# eps_digital.net
KiCad netlist of a schematic drawn in Altium Designer
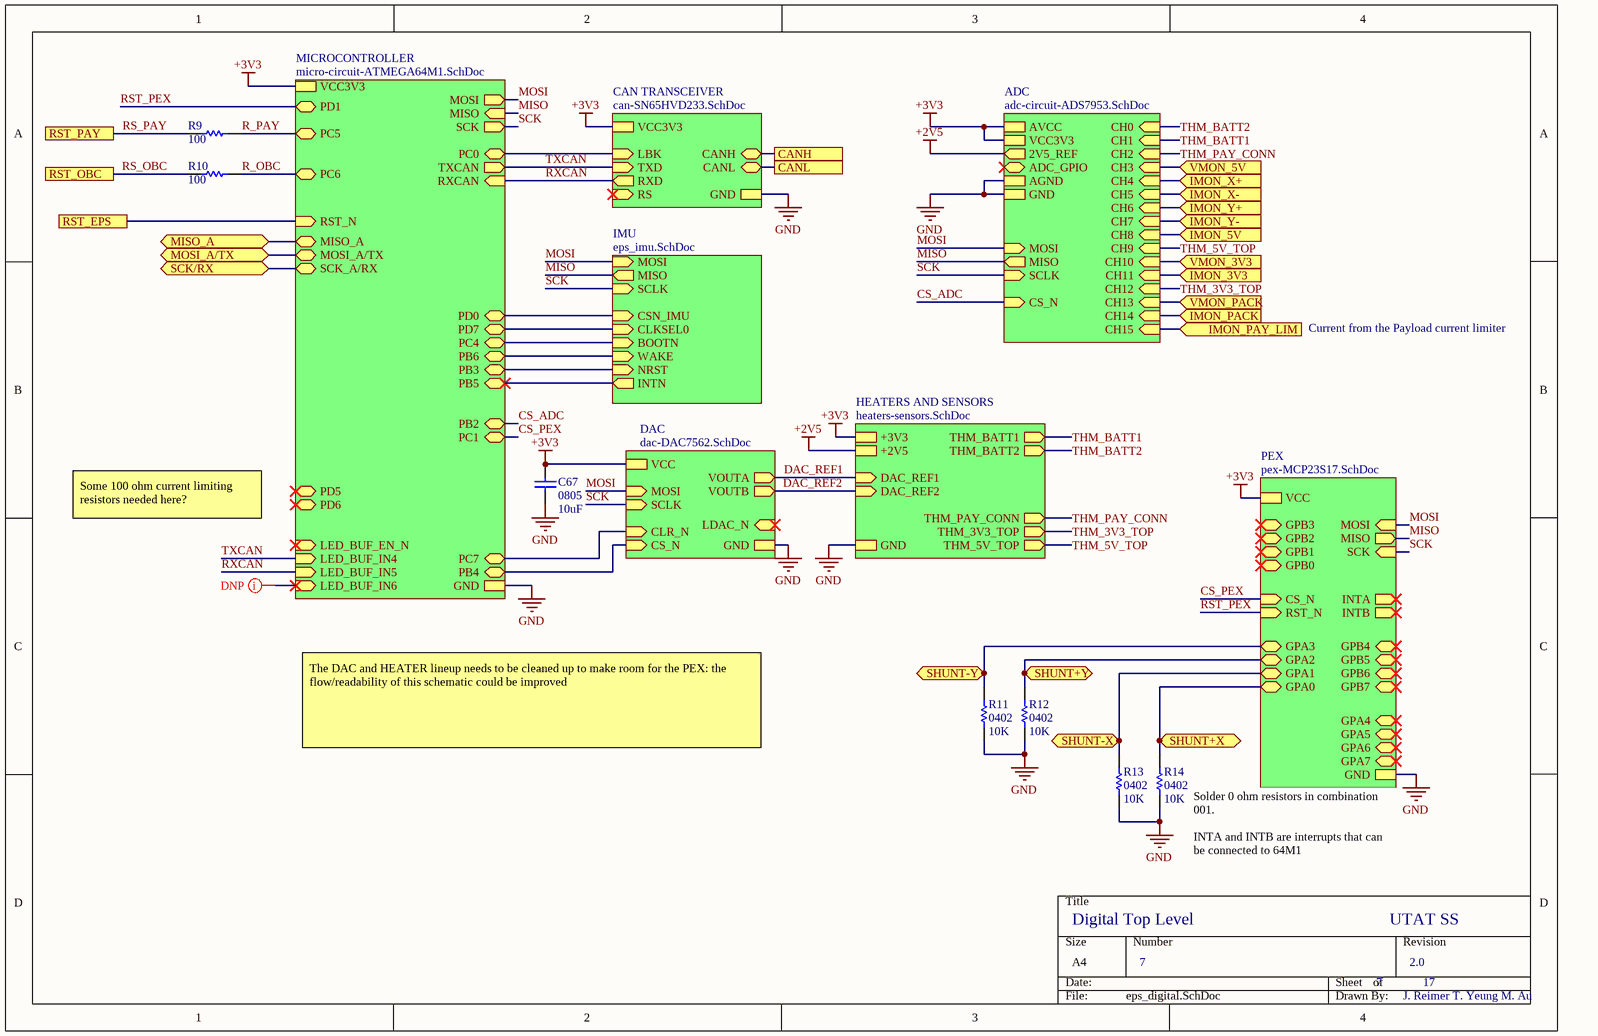
[diagram p0: eps_digital.SchDoc]

(export (version "E")
  (design (tool "Eeschema 10.0.6"))
  (components
    (comp (ref "C67")
      (value "0805")
      (footprint "CAP0805R")
      (description "0805 capacitor")
      (fields (field (name "ALTIUM_VALUE") "10uF"))
      (libsource (lib "heron-general") (part "CAP0805"))
    )
    (comp (ref "R9")
      (value "100")
      (footprint "RES0402R")
      (description "0402 resistor")
      (fields (field (name "Comment") "0402"))
      (libsource (lib "heron-general") (part "RES0402"))
    )
    (comp (ref "R10")
      (value "100")
      (footprint "RES0402R")
      (description "0402 resistor")
      (fields (field (name "Comment") "0402"))
      (libsource (lib "heron-general") (part "RES0402"))
    )
    (comp (ref "R11")
      (value "0402")
      (footprint "RES0402R")
      (description "0402 resistor")
      (fields (field (name "ALTIUM_VALUE") "10K"))
      (libsource (lib "heron-general") (part "RES0402"))
    )
    (comp (ref "R12")
      (value "0402")
      (footprint "RES0402R")
      (description "0402 resistor")
      (fields (field (name "ALTIUM_VALUE") "10K"))
      (libsource (lib "heron-general") (part "RES0402"))
    )
    (comp (ref "R13")
      (value "0402")
      (footprint "RES0402R")
      (description "0402 resistor")
      (fields (field (name "ALTIUM_VALUE") "10K"))
      (libsource (lib "heron-general") (part "RES0402"))
    )
    (comp (ref "R14")
      (value "0402")
      (footprint "RES0402R")
      (description "0402 resistor")
      (fields (field (name "ALTIUM_VALUE") "10K"))
      (libsource (lib "heron-general") (part "RES0402"))
    )
  )
  (nets
    (net (code "2") (name "+3V3") (class "Default")
      (node (ref "C67") (pin "2") (pinfunction "2_2") (pintype "passive"))
    )
    (net (code "53") (name "/RS_OBC") (class "Default")
      (node (ref "R10") (pin "1") (pinfunction "1_1") (pintype "passive"))
    )
    (net (code "54") (name "/RS_PAY") (class "Default")
      (node (ref "R9") (pin "1") (pinfunction "1_1") (pintype "passive"))
    )
    (net (code "56") (name "/R_OBC") (class "Default")
      (node (ref "R10") (pin "2") (pinfunction "2_2") (pintype "passive"))
    )
    (net (code "57") (name "/R_PAY") (class "Default")
      (node (ref "R9") (pin "2") (pinfunction "2_2") (pintype "passive"))
    )
    (net (code "60") (name "/SHUNT+X") (class "Default")
      (node (ref "R14") (pin "2") (pinfunction "2_2") (pintype "passive"))
    )
    (net (code "61") (name "/SHUNT+Y") (class "Default")
      (node (ref "R12") (pin "2") (pinfunction "2_2") (pintype "passive"))
    )
    (net (code "62") (name "/SHUNT-X") (class "Default")
      (node (ref "R13") (pin "2") (pinfunction "2_2") (pintype "passive"))
    )
    (net (code "63") (name "/SHUNT-Y") (class "Default")
      (node (ref "R11") (pin "2") (pinfunction "2_2") (pintype "passive"))
    )
    (net (code "73") (name "GND") (class "Default")
      (node (ref "C67") (pin "1") (pinfunction "1_1") (pintype "passive"))
      (node (ref "R11") (pin "1") (pinfunction "1_1") (pintype "passive"))
      (node (ref "R12") (pin "1") (pinfunction "1_1") (pintype "passive"))
      (node (ref "R13") (pin "1") (pinfunction "1_1") (pintype "passive"))
      (node (ref "R14") (pin "1") (pinfunction "1_1") (pintype "passive"))
    )
  )
)
